# FMC_DAC_125M_14B_16CHA.net
KiCad netlist of a schematic drawn in Altium Designer
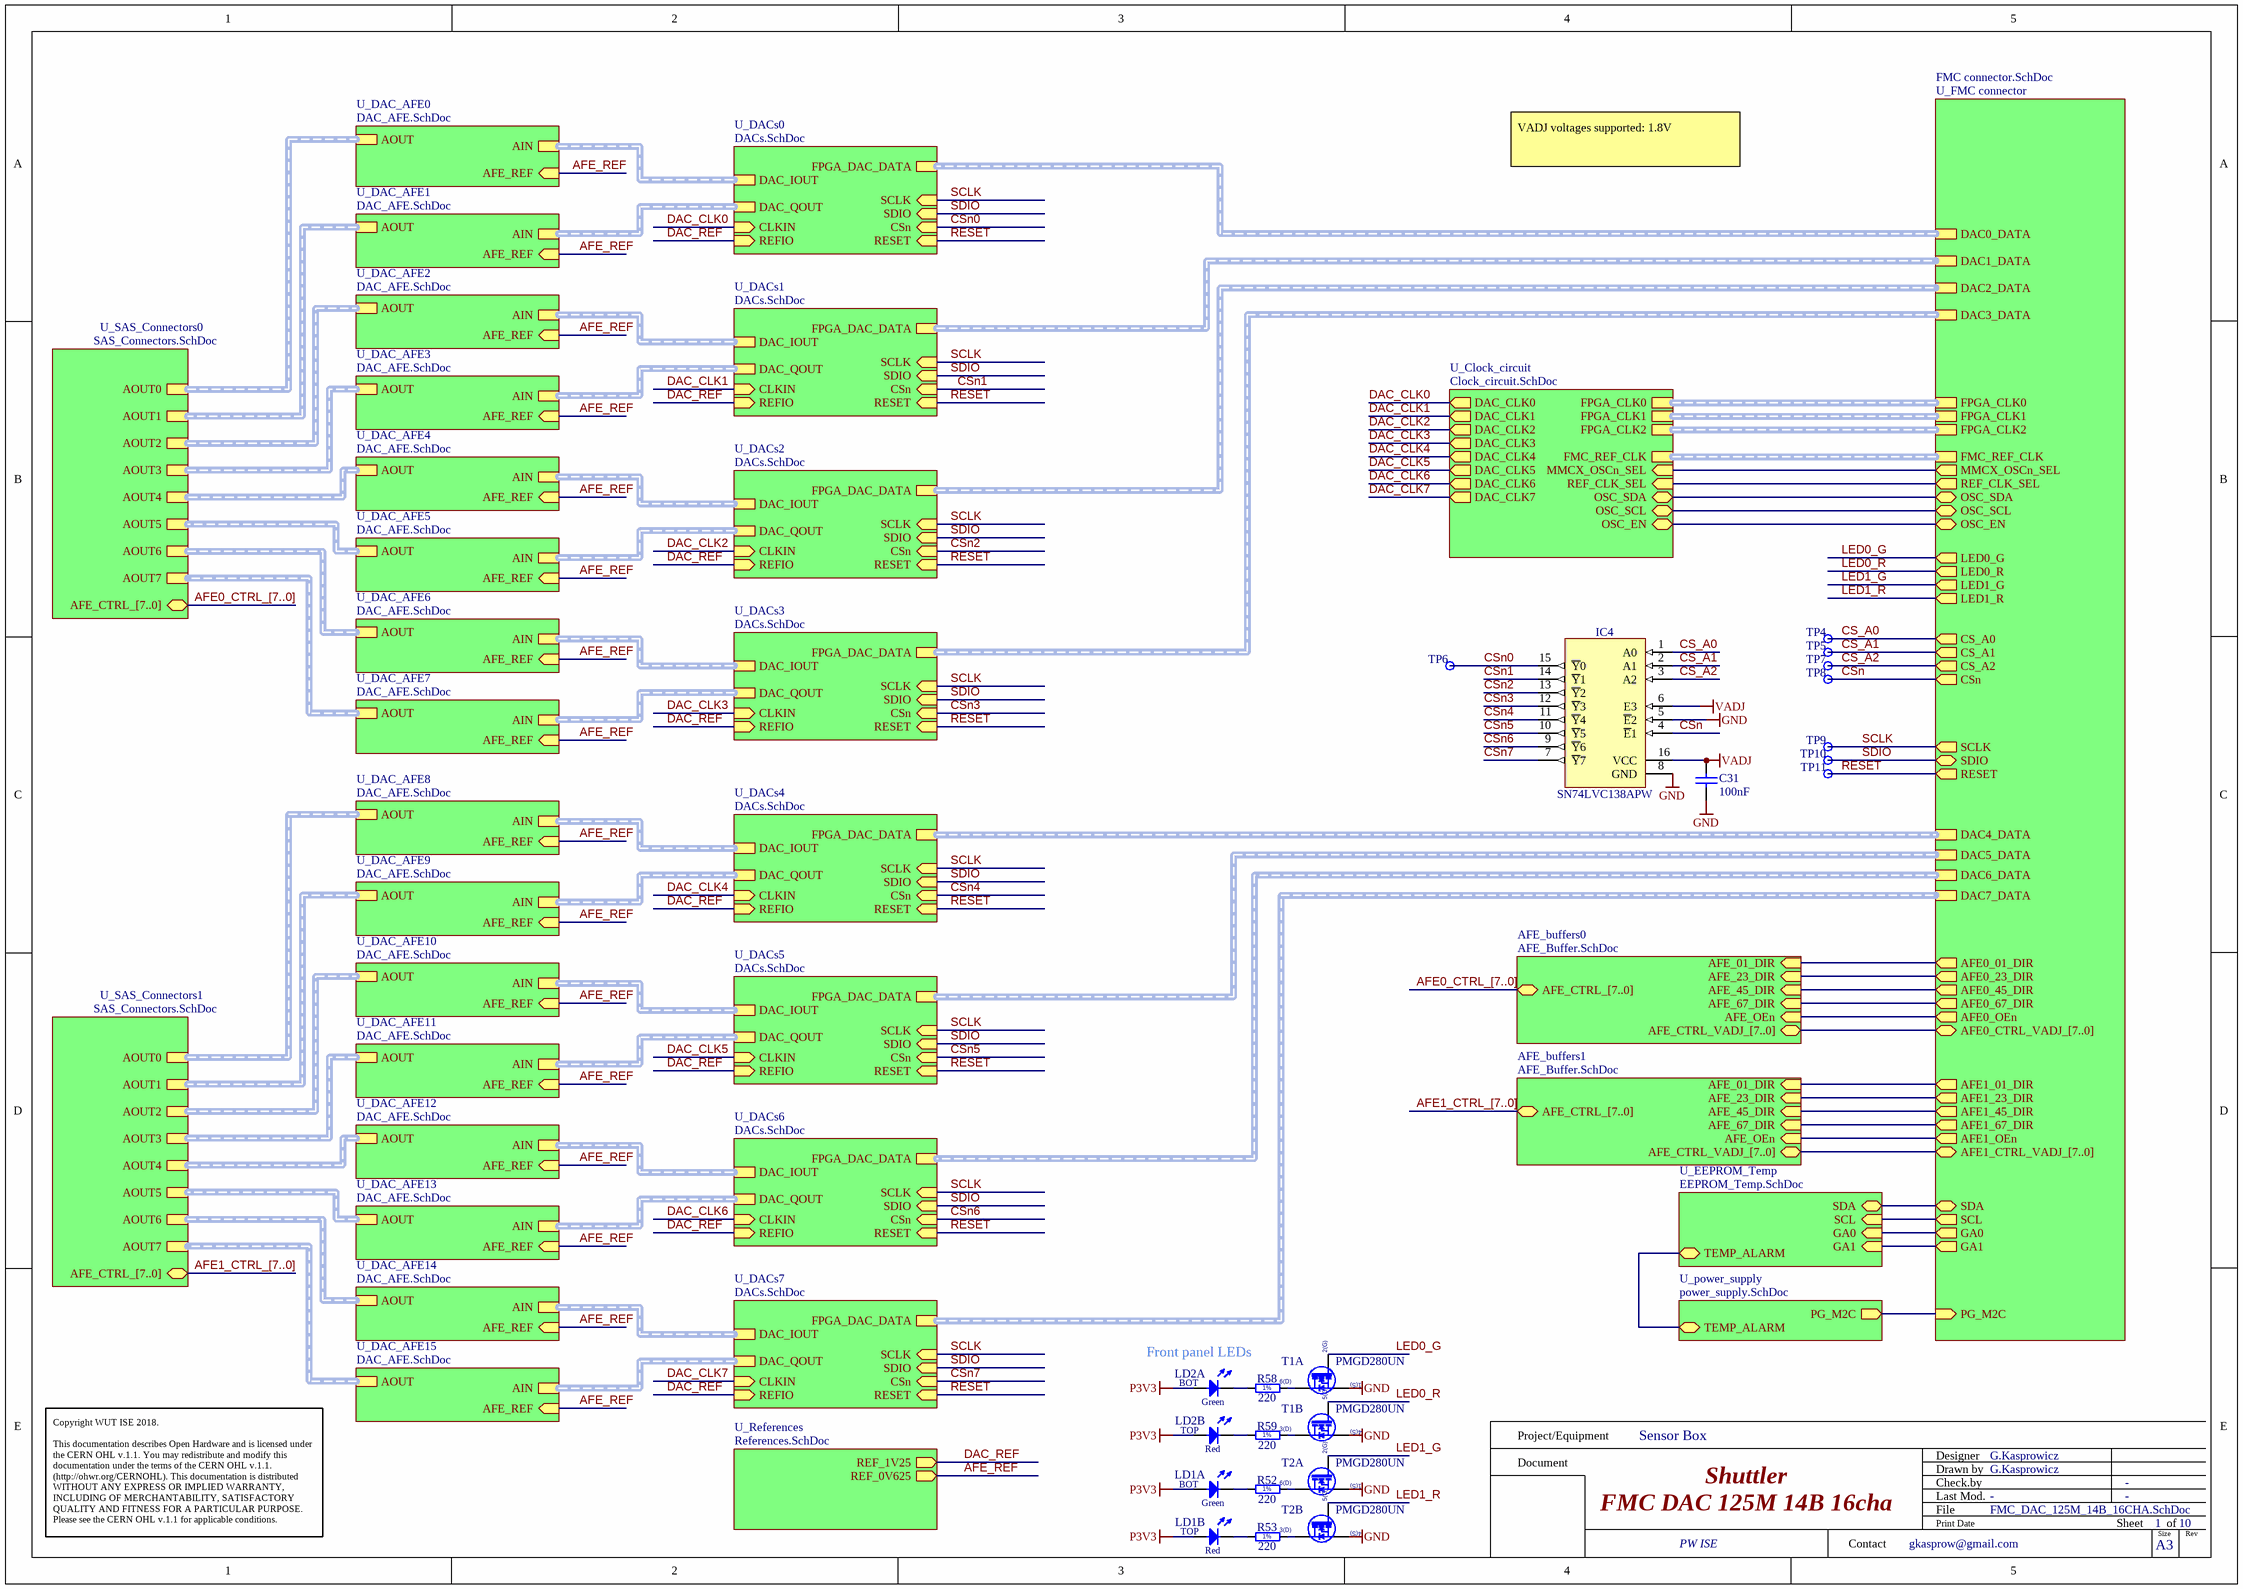
[diagram p0: FMC_DAC_125M_14B_16CHA.SchDoc]

(export (version "E")
  (design (tool "Eeschema 10.0.6"))
  (components
    (comp (ref "C31")
      (value "100nF")
      (footprint "CAPC1005X55N")
      (description "Non-polarised capacitor")
      (fields
        (field (name "PART NUMBER") "CC0402_100NF_16V_10%_X5R")
        (field (name "VOLTAGE") "16V")
        (field (name "AUTHOR") "CERN DEM JLC")
      )
      (libsource (lib "Capacitors") (part "Capacitor - non polarized"))
    )
    (comp (ref "IC4")
      (value "SN74LVC138APW")
      (footprint "SOP65P640X110-16N")
      (description "3-Line to 8-Line Decoder/Demultiplexer")
      (fields (field (name "MANUFACTURER") "Texas Instruments") (field (name "AUTHOR") "GK"))
      (libsource (lib "ICS-logic") (part "SN74LVC138APW"))
    )
    (comp (ref "LD1")
      (value "Red/Green")
      (footprint "LED_DIALIGHT_571-0112F")
      (description "2x LED  Botom Green, Top Red")
      (fields
        (field (name "PART NUMBER") "LED_DIALIGHT_571-0112F")
        (field (name "MANUFACTURER") "DIALIGHT")
        (field (name "AUTHOR") "CERN DEM JLC")
      )
      (libsource (lib "ICs And Semiconductors") (part "LED x2 G-1C2A-BOT_R-3C4A-TOP"))
    )
    (comp (ref "LD2")
      (value "Red/Green")
      (footprint "LED_DIALIGHT_571-0112F")
      (description "2x LED  Botom Green, Top Red")
      (fields
        (field (name "PART NUMBER") "LED_DIALIGHT_571-0112F")
        (field (name "MANUFACTURER") "DIALIGHT")
        (field (name "AUTHOR") "CERN DEM JLC")
      )
      (libsource (lib "ICs And Semiconductors") (part "LED x2 G-1C2A-BOT_R-3C4A-TOP"))
    )
    (comp (ref "R52")
      (value "220")
      (footprint "RESC1608X55N")
      (description "Resistor - 1%")
      (fields
        (field (name "PART NUMBER") "R0603_220R_1%_0.1W_100PPM")
        (field (name "POWER") "0.1W")
        (field (name "AUTHOR") "CERN DEM JLC")
      )
      (libsource (lib "Resistors") (part "Resistor - 1%"))
    )
    (comp (ref "R53")
      (value "220")
      (footprint "RESC1608X55N")
      (description "Resistor - 1%")
      (fields
        (field (name "PART NUMBER") "R0603_220R_1%_0.1W_100PPM")
        (field (name "POWER") "0.1W")
        (field (name "AUTHOR") "CERN DEM JLC")
      )
      (libsource (lib "Resistors") (part "Resistor - 1%"))
    )
    (comp (ref "R58")
      (value "220")
      (footprint "RESC1608X55N")
      (description "Resistor - 1%")
      (fields
        (field (name "PART NUMBER") "R0603_220R_1%_0.1W_100PPM")
        (field (name "POWER") "0.1W")
        (field (name "AUTHOR") "CERN DEM JLC")
      )
      (libsource (lib "Resistors") (part "Resistor - 1%"))
    )
    (comp (ref "R59")
      (value "220")
      (footprint "RESC1608X55N")
      (description "Resistor - 1%")
      (fields
        (field (name "PART NUMBER") "R0603_220R_1%_0.1W_100PPM")
        (field (name "POWER") "0.1W")
        (field (name "AUTHOR") "CERN DEM JLC")
      )
      (libsource (lib "Resistors") (part "Resistor - 1%"))
    )
    (comp (ref "T1")
      (value "PMGD280UN")
      (footprint "SOT65P210X110-6N")
      (description "Dual N-Channel micro TrenchMOS™ Ultra Low Level FET")
      (fields (field (name "MANUFACTURER") "NXP SEMICONDUCTORS") (field (name "AUTHOR") "CERN DEM JLC"))
      (libsource (lib "") (part "PMGD280UN_1"))
    )
    (comp (ref "T2")
      (value "PMGD280UN")
      (footprint "SOT65P210X110-6N")
      (description "Dual N-Channel micro TrenchMOS™ Ultra Low Level FET")
      (fields (field (name "MANUFACTURER") "NXP SEMICONDUCTORS") (field (name "AUTHOR") "CERN DEM JLC"))
      (libsource (lib "") (part "PMGD280UN_1"))
    )
    (comp (ref "TP4")
      (value "Test Point")
      (footprint "TPS127")
      (fields (field (name "PART NUMBER") "SMD_PAD_1.27X1.27MM") (field (name "AUTHOR") "CERN DEM JLC"))
      (libsource (lib "Eletro-mechanical") (part "Test Point"))
    )
    (comp (ref "TP5")
      (value "Test Point")
      (footprint "TPS127")
      (fields (field (name "PART NUMBER") "SMD_PAD_1.27X1.27MM") (field (name "AUTHOR") "CERN DEM JLC"))
      (libsource (lib "Eletro-mechanical") (part "Test Point"))
    )
    (comp (ref "TP6")
      (value "Test Point")
      (footprint "TPS127")
      (fields (field (name "PART NUMBER") "SMD_PAD_1.27X1.27MM") (field (name "AUTHOR") "CERN DEM JLC"))
      (libsource (lib "Eletro-mechanical") (part "Test Point"))
    )
    (comp (ref "TP7")
      (value "Test Point")
      (footprint "TPS127")
      (fields (field (name "PART NUMBER") "SMD_PAD_1.27X1.27MM") (field (name "AUTHOR") "CERN DEM JLC"))
      (libsource (lib "Eletro-mechanical") (part "Test Point"))
    )
    (comp (ref "TP8")
      (value "Test Point")
      (footprint "TPS127")
      (fields (field (name "PART NUMBER") "SMD_PAD_1.27X1.27MM") (field (name "AUTHOR") "CERN DEM JLC"))
      (libsource (lib "Eletro-mechanical") (part "Test Point"))
    )
    (comp (ref "TP9")
      (value "Test Point")
      (footprint "TPS127")
      (fields (field (name "PART NUMBER") "SMD_PAD_1.27X1.27MM") (field (name "AUTHOR") "CERN DEM JLC"))
      (libsource (lib "Eletro-mechanical") (part "Test Point"))
    )
    (comp (ref "TP10")
      (value "Test Point")
      (footprint "TPS127")
      (fields (field (name "PART NUMBER") "SMD_PAD_1.27X1.27MM") (field (name "AUTHOR") "CERN DEM JLC"))
      (libsource (lib "Eletro-mechanical") (part "Test Point"))
    )
    (comp (ref "TP11")
      (value "Test Point")
      (footprint "TPS127")
      (fields (field (name "PART NUMBER") "SMD_PAD_1.27X1.27MM") (field (name "AUTHOR") "CERN DEM JLC"))
      (libsource (lib "Eletro-mechanical") (part "Test Point"))
    )
  )
  (nets
    (net (code "64") (name "/CS_A0") (class "Default")
      (node (ref "IC4") (pin "1") (pinfunction "A0_1") (pintype "input"))
      (node (ref "TP4") (pin "1") (pinfunction "1_1") (pintype "bidirectional"))
    )
    (net (code "65") (name "/CS_A1") (class "Default")
      (node (ref "IC4") (pin "2") (pinfunction "A1_2") (pintype "input"))
      (node (ref "TP5") (pin "1") (pinfunction "1_1") (pintype "bidirectional"))
    )
    (net (code "66") (name "/CS_A2") (class "Default")
      (node (ref "IC4") (pin "3") (pinfunction "A2_3") (pintype "input"))
      (node (ref "TP7") (pin "1") (pinfunction "1_1") (pintype "bidirectional"))
    )
    (net (code "67") (name "/CSn") (class "Default")
      (node (ref "IC4") (pin "4") (pinfunction "~{E}1_4") (pintype "input"))
      (node (ref "TP8") (pin "1") (pinfunction "1_1") (pintype "bidirectional"))
    )
    (net (code "68") (name "/CSn0") (class "Default")
      (node (ref "IC4") (pin "15") (pinfunction "~{Y}0_15") (pintype "output"))
      (node (ref "TP6") (pin "1") (pinfunction "1_1") (pintype "bidirectional"))
    )
    (net (code "69") (name "/CSn1") (class "Default")
      (node (ref "IC4") (pin "14") (pinfunction "~{Y}1_14") (pintype "output"))
    )
    (net (code "70") (name "/CSn2") (class "Default")
      (node (ref "IC4") (pin "13") (pinfunction "~{Y}2_13") (pintype "output"))
    )
    (net (code "71") (name "/CSn3") (class "Default")
      (node (ref "IC4") (pin "12") (pinfunction "~{Y}3_12") (pintype "output"))
    )
    (net (code "72") (name "/CSn4") (class "Default")
      (node (ref "IC4") (pin "11") (pinfunction "~{Y}4_11") (pintype "output"))
    )
    (net (code "73") (name "/CSn5") (class "Default")
      (node (ref "IC4") (pin "10") (pinfunction "~{Y}5_10") (pintype "output"))
    )
    (net (code "74") (name "/CSn6") (class "Default")
      (node (ref "IC4") (pin "9") (pinfunction "~{Y}6_9") (pintype "output"))
    )
    (net (code "75") (name "/CSn7") (class "Default")
      (node (ref "IC4") (pin "7") (pinfunction "~{Y}7_7") (pintype "output"))
    )
    (net (code "99") (name "/LED0_G") (class "Default")
      (node (ref "T1") (pin "2") (pinfunction "G_2") (pintype "passive"))
    )
    (net (code "100") (name "/LED0_R") (class "Default")
      (node (ref "T1") (pin "5") (pinfunction "G_5") (pintype "passive"))
    )
    (net (code "101") (name "/LED1_G") (class "Default")
      (node (ref "T2") (pin "2") (pinfunction "G_2") (pintype "passive"))
    )
    (net (code "102") (name "/LED1_R") (class "Default")
      (node (ref "T2") (pin "5") (pinfunction "G_5") (pintype "passive"))
    )
    (net (code "109") (name "/RESET") (class "Default")
      (node (ref "TP11") (pin "1") (pinfunction "1_1") (pintype "bidirectional"))
    )
    (net (code "111") (name "/SCLK") (class "Default")
      (node (ref "TP9") (pin "1") (pinfunction "1_1") (pintype "bidirectional"))
    )
    (net (code "113") (name "/SDIO") (class "Default")
      (node (ref "TP10") (pin "1") (pinfunction "1_1") (pintype "bidirectional"))
    )
    (net (code "115") (name "GND") (class "Default")
      (node (ref "C31") (pin "1") (pinfunction "1_1") (pintype "passive"))
      (node (ref "IC4") (pin "5") (pinfunction "~{E}2_5") (pintype "input"))
      (node (ref "IC4") (pin "8") (pinfunction "GND_8") (pintype "power_in"))
      (node (ref "T1") (pin "1") (pinfunction "S_1") (pintype "passive"))
      (node (ref "T1") (pin "4") (pinfunction "S_4") (pintype "passive"))
      (node (ref "T2") (pin "1") (pinfunction "S_1") (pintype "passive"))
      (node (ref "T2") (pin "4") (pinfunction "S_4") (pintype "passive"))
    )
    (net (code "116") (name "Net-(LD1A-C)") (class "Default")
      (node (ref "LD1") (pin "1") (pinfunction "C_1") (pintype "passive"))
      (node (ref "R52") (pin "1") (pinfunction "1_1") (pintype "passive"))
    )
    (net (code "117") (name "Net-(LD1B-C)") (class "Default")
      (node (ref "LD1") (pin "3") (pinfunction "C_3") (pintype "passive"))
      (node (ref "R53") (pin "1") (pinfunction "1_1") (pintype "passive"))
    )
    (net (code "118") (name "Net-(LD2A-C)") (class "Default")
      (node (ref "LD2") (pin "1") (pinfunction "C_1") (pintype "passive"))
      (node (ref "R58") (pin "1") (pinfunction "1_1") (pintype "passive"))
    )
    (net (code "119") (name "Net-(LD2B-C)") (class "Default")
      (node (ref "LD2") (pin "3") (pinfunction "C_3") (pintype "passive"))
      (node (ref "R59") (pin "1") (pinfunction "1_1") (pintype "passive"))
    )
    (net (code "120") (name "Net-(T1A-D)") (class "Default")
      (node (ref "R58") (pin "2") (pinfunction "2_2") (pintype "passive"))
      (node (ref "T1") (pin "6") (pinfunction "D_6") (pintype "passive"))
    )
    (net (code "121") (name "Net-(T1B-D)") (class "Default")
      (node (ref "R59") (pin "2") (pinfunction "2_2") (pintype "passive"))
      (node (ref "T1") (pin "3") (pinfunction "D_3") (pintype "passive"))
    )
    (net (code "122") (name "Net-(T2A-D)") (class "Default")
      (node (ref "R52") (pin "2") (pinfunction "2_2") (pintype "passive"))
      (node (ref "T2") (pin "6") (pinfunction "D_6") (pintype "passive"))
    )
    (net (code "123") (name "Net-(T2B-D)") (class "Default")
      (node (ref "R53") (pin "2") (pinfunction "2_2") (pintype "passive"))
      (node (ref "T2") (pin "3") (pinfunction "D_3") (pintype "passive"))
    )
    (net (code "124") (name "P3V3") (class "Default")
      (node (ref "LD1") (pin "2") (pinfunction "A_2") (pintype "passive"))
      (node (ref "LD1") (pin "4") (pinfunction "A_4") (pintype "passive"))
      (node (ref "LD2") (pin "2") (pinfunction "A_2") (pintype "passive"))
      (node (ref "LD2") (pin "4") (pinfunction "A_4") (pintype "passive"))
    )
    (net (code "125") (name "VADJ") (class "Default")
      (node (ref "C31") (pin "2") (pinfunction "2_2") (pintype "passive"))
      (node (ref "IC4") (pin "16") (pinfunction "VCC_16") (pintype "power_in"))
      (node (ref "IC4") (pin "6") (pinfunction "E3_6") (pintype "input"))
    )
  )
)
